# SAO_Area3001_L_WS2812_00.net
KiCad netlist of a schematic drawn in Altium Designer
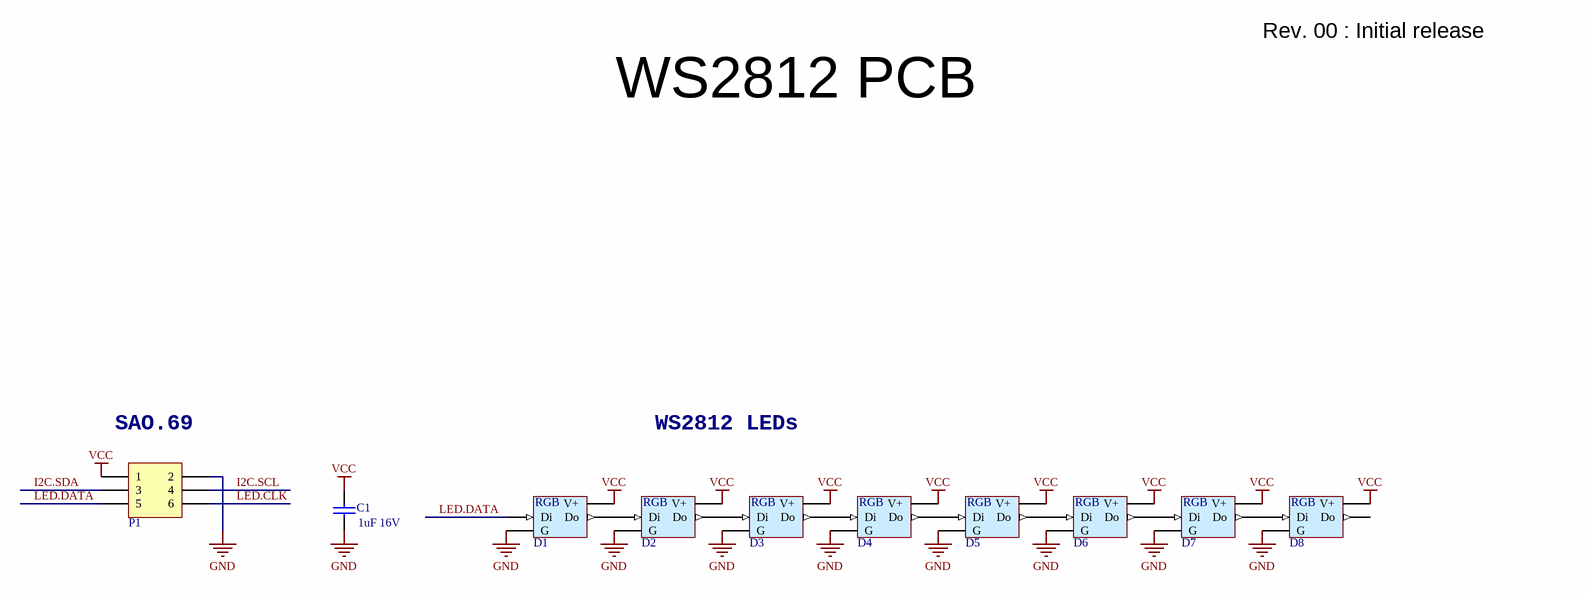
[diagram p0: SAO_Area3001_L_WS2812_00.SchDoc]

(export (version "E")
  (design (tool "Eeschema 10.0.6"))
  (components
    (comp (ref "C1")
      (value "1uF 16V")
      (footprint "C0603_N")
      (description "Capacitor Ceramic")
      (fields (field (name "Comment") "CAP_CERAMIC"))
      (libsource (lib "Phyx_Components") (part "CAP_CERAMIC"))
    )
    (comp (ref "D1")
      (value "WS2812 based digital RGB LED 5050 White package")
      (footprint "LED_5050_WS2812B_WHITE")
      (description "=Description")
      (libsource (lib "Phyx_Components") (part "LED_RGB_WS2812B_5050"))
    )
    (comp (ref "D2")
      (value "WS2812 based digital RGB LED 5050 White package")
      (footprint "LED_5050_WS2812B_WHITE")
      (description "=Description")
      (libsource (lib "Phyx_Components") (part "LED_RGB_WS2812B_5050"))
    )
    (comp (ref "D3")
      (value "WS2812 based digital RGB LED 5050 White package")
      (footprint "LED_5050_WS2812B_WHITE")
      (description "=Description")
      (libsource (lib "Phyx_Components") (part "LED_RGB_WS2812B_5050"))
    )
    (comp (ref "D4")
      (value "WS2812 based digital RGB LED 5050 White package")
      (footprint "LED_5050_WS2812B_WHITE")
      (description "=Description")
      (libsource (lib "Phyx_Components") (part "LED_RGB_WS2812B_5050"))
    )
    (comp (ref "D5")
      (value "WS2812 based digital RGB LED 5050 White package")
      (footprint "LED_5050_WS2812B_WHITE")
      (description "=Description")
      (libsource (lib "Phyx_Components") (part "LED_RGB_WS2812B_5050"))
    )
    (comp (ref "D6")
      (value "WS2812 based digital RGB LED 5050 White package")
      (footprint "LED_5050_WS2812B_WHITE")
      (description "=Description")
      (libsource (lib "Phyx_Components") (part "LED_RGB_WS2812B_5050"))
    )
    (comp (ref "D7")
      (value "WS2812 based digital RGB LED 5050 White package")
      (footprint "LED_5050_WS2812B_WHITE")
      (description "=Description")
      (libsource (lib "Phyx_Components") (part "LED_RGB_WS2812B_5050"))
    )
    (comp (ref "D8")
      (value "WS2812 based digital RGB LED 5050 White package")
      (footprint "LED_5050_WS2812B_WHITE")
      (description "=Description")
      (libsource (lib "Phyx_Components") (part "LED_RGB_WS2812B_5050"))
    )
    (comp (ref "P1")
      (value "Boxed Header 3X2")
      (footprint "B_HDR2X3")
      (libsource (lib "Phyx_Components") (part "Header 3X2"))
    )
  )
  (nets
    (net (code "1") (name "/I2C.SCL") (class "Default")
      (node (ref "P1") (pin "4") (pinfunction "4_4") (pintype "passive"))
    )
    (net (code "2") (name "/I2C.SDA") (class "Default")
      (node (ref "P1") (pin "3") (pinfunction "3_3") (pintype "passive"))
    )
    (net (code "3") (name "/LED.CLK") (class "Default")
      (node (ref "P1") (pin "6") (pinfunction "6_6") (pintype "passive"))
    )
    (net (code "4") (name "/LED.DATA") (class "Default")
      (node (ref "D1") (pin "4") (pinfunction "Di_4") (pintype "input"))
      (node (ref "P1") (pin "5") (pinfunction "5_5") (pintype "passive"))
    )
    (net (code "5") (name "GND") (class "Default")
      (node (ref "C1") (pin "2") (pinfunction "2_2") (pintype "passive"))
      (node (ref "D1") (pin "3") (pinfunction "G_3") (pintype "power_in"))
      (node (ref "D2") (pin "3") (pinfunction "G_3") (pintype "power_in"))
      (node (ref "D3") (pin "3") (pinfunction "G_3") (pintype "power_in"))
      (node (ref "D4") (pin "3") (pinfunction "G_3") (pintype "power_in"))
      (node (ref "D5") (pin "3") (pinfunction "G_3") (pintype "power_in"))
      (node (ref "D6") (pin "3") (pinfunction "G_3") (pintype "power_in"))
      (node (ref "D7") (pin "3") (pinfunction "G_3") (pintype "power_in"))
      (node (ref "D8") (pin "3") (pinfunction "G_3") (pintype "power_in"))
      (node (ref "P1") (pin "2") (pinfunction "2_2") (pintype "passive"))
    )
    (net (code "6") (name "Net-(D1-Do)") (class "Default")
      (node (ref "D1") (pin "2") (pinfunction "Do_2") (pintype "output"))
      (node (ref "D2") (pin "4") (pinfunction "Di_4") (pintype "input"))
    )
    (net (code "7") (name "Net-(D2-Do)") (class "Default")
      (node (ref "D2") (pin "2") (pinfunction "Do_2") (pintype "output"))
      (node (ref "D3") (pin "4") (pinfunction "Di_4") (pintype "input"))
    )
    (net (code "8") (name "Net-(D3-Do)") (class "Default")
      (node (ref "D3") (pin "2") (pinfunction "Do_2") (pintype "output"))
      (node (ref "D4") (pin "4") (pinfunction "Di_4") (pintype "input"))
    )
    (net (code "9") (name "Net-(D4-Do)") (class "Default")
      (node (ref "D4") (pin "2") (pinfunction "Do_2") (pintype "output"))
      (node (ref "D5") (pin "4") (pinfunction "Di_4") (pintype "input"))
    )
    (net (code "10") (name "Net-(D5-Do)") (class "Default")
      (node (ref "D5") (pin "2") (pinfunction "Do_2") (pintype "output"))
      (node (ref "D6") (pin "4") (pinfunction "Di_4") (pintype "input"))
    )
    (net (code "11") (name "Net-(D6-Do)") (class "Default")
      (node (ref "D6") (pin "2") (pinfunction "Do_2") (pintype "output"))
      (node (ref "D7") (pin "4") (pinfunction "Di_4") (pintype "input"))
    )
    (net (code "12") (name "Net-(D7-Do)") (class "Default")
      (node (ref "D7") (pin "2") (pinfunction "Do_2") (pintype "output"))
      (node (ref "D8") (pin "4") (pinfunction "Di_4") (pintype "input"))
    )
    (net (code "13") (name "VCC") (class "Default")
      (node (ref "C1") (pin "1") (pinfunction "1_1") (pintype "passive"))
      (node (ref "D1") (pin "1") (pinfunction "V+_1") (pintype "power_in"))
      (node (ref "D2") (pin "1") (pinfunction "V+_1") (pintype "power_in"))
      (node (ref "D3") (pin "1") (pinfunction "V+_1") (pintype "power_in"))
      (node (ref "D4") (pin "1") (pinfunction "V+_1") (pintype "power_in"))
      (node (ref "D5") (pin "1") (pinfunction "V+_1") (pintype "power_in"))
      (node (ref "D6") (pin "1") (pinfunction "V+_1") (pintype "power_in"))
      (node (ref "D7") (pin "1") (pinfunction "V+_1") (pintype "power_in"))
      (node (ref "D8") (pin "1") (pinfunction "V+_1") (pintype "power_in"))
      (node (ref "P1") (pin "1") (pinfunction "1_1") (pintype "passive"))
    )
    (net (code "14") (name "unconnected-(D8-Do-Pad2)") (class "Default")
      (node (ref "D8") (pin "2") (pinfunction "Do_2") (pintype "output"))
    )
  )
)
